# P07_DDR3.net
KiCad netlist of a schematic drawn in Altium Designer
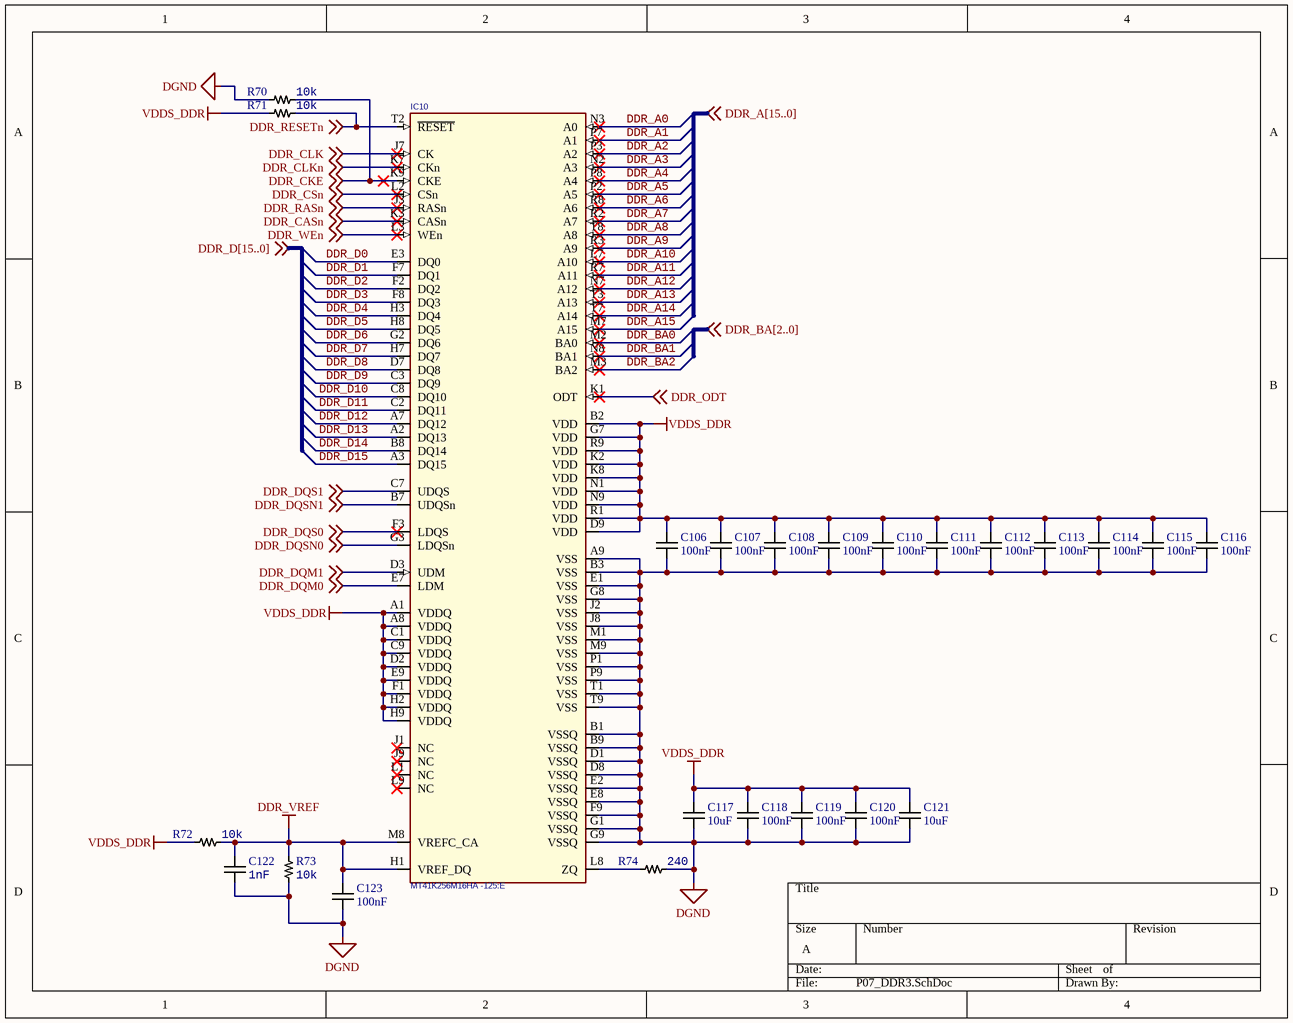
[diagram p0: P07_DDR3.SchDoc]

(export (version "E")
  (design (tool "Eeschema 10.0.6"))
  (components
    (comp (ref "C106")
      (value "C0402C104K4RACTU")
      (footprint "Orient:CAP0402")
      (description "MLCC 100nF 0402 SMD")
      (fields
        (field (name "MANUFACTURER") "KEMET")
        (field (name "CAPACITANCE") "100nF")
        (field (name "TOLERANCE") "10%")
      )
      (libsource (lib "Orient") (part "CAP_100nF"))
    )
    (comp (ref "C107")
      (value "C0402C104K4RACTU")
      (footprint "Orient:CAP0402")
      (description "MLCC 100nF 0402 SMD")
      (fields
        (field (name "MANUFACTURER") "KEMET")
        (field (name "CAPACITANCE") "100nF")
        (field (name "TOLERANCE") "10%")
      )
      (libsource (lib "Orient") (part "CAP_100nF"))
    )
    (comp (ref "C108")
      (value "C0402C104K4RACTU")
      (footprint "Orient:CAP0402")
      (description "MLCC 100nF 0402 SMD")
      (fields
        (field (name "MANUFACTURER") "KEMET")
        (field (name "CAPACITANCE") "100nF")
        (field (name "TOLERANCE") "10%")
      )
      (libsource (lib "Orient") (part "CAP_100nF"))
    )
    (comp (ref "C109")
      (value "C0402C104K4RACTU")
      (footprint "Orient:CAP0402")
      (description "MLCC 100nF 0402 SMD")
      (fields
        (field (name "MANUFACTURER") "KEMET")
        (field (name "CAPACITANCE") "100nF")
        (field (name "TOLERANCE") "10%")
      )
      (libsource (lib "Orient") (part "CAP_100nF"))
    )
    (comp (ref "C110")
      (value "C0402C104K4RACTU")
      (footprint "Orient:CAP0402")
      (description "MLCC 100nF 0402 SMD")
      (fields
        (field (name "MANUFACTURER") "KEMET")
        (field (name "CAPACITANCE") "100nF")
        (field (name "TOLERANCE") "10%")
      )
      (libsource (lib "Orient") (part "CAP_100nF"))
    )
    (comp (ref "C111")
      (value "C0402C104K4RACTU")
      (footprint "Orient:CAP0402")
      (description "MLCC 100nF 0402 SMD")
      (fields
        (field (name "MANUFACTURER") "KEMET")
        (field (name "CAPACITANCE") "100nF")
        (field (name "TOLERANCE") "10%")
      )
      (libsource (lib "Orient") (part "CAP_100nF"))
    )
    (comp (ref "C112")
      (value "C0402C104K4RACTU")
      (footprint "Orient:CAP0402")
      (description "MLCC 100nF 0402 SMD")
      (fields
        (field (name "MANUFACTURER") "KEMET")
        (field (name "CAPACITANCE") "100nF")
        (field (name "TOLERANCE") "10%")
      )
      (libsource (lib "Orient") (part "CAP_100nF"))
    )
    (comp (ref "C113")
      (value "C0402C104K4RACTU")
      (footprint "Orient:CAP0402")
      (description "MLCC 100nF 0402 SMD")
      (fields
        (field (name "MANUFACTURER") "KEMET")
        (field (name "CAPACITANCE") "100nF")
        (field (name "TOLERANCE") "10%")
      )
      (libsource (lib "Orient") (part "CAP_100nF"))
    )
    (comp (ref "C114")
      (value "C0402C104K4RACTU")
      (footprint "Orient:CAP0402")
      (description "MLCC 100nF 0402 SMD")
      (fields
        (field (name "MANUFACTURER") "KEMET")
        (field (name "CAPACITANCE") "100nF")
        (field (name "TOLERANCE") "10%")
      )
      (libsource (lib "Orient") (part "CAP_100nF"))
    )
    (comp (ref "C115")
      (value "C0402C104K4RACTU")
      (footprint "Orient:CAP0402")
      (description "MLCC 100nF 0402 SMD")
      (fields
        (field (name "MANUFACTURER") "KEMET")
        (field (name "CAPACITANCE") "100nF")
        (field (name "TOLERANCE") "10%")
      )
      (libsource (lib "Orient") (part "CAP_100nF"))
    )
    (comp (ref "C116")
      (value "C0402C104K4RACTU")
      (footprint "Orient:CAP0402")
      (description "MLCC 100nF 0402 SMD")
      (fields
        (field (name "MANUFACTURER") "KEMET")
        (field (name "CAPACITANCE") "100nF")
        (field (name "TOLERANCE") "10%")
      )
      (libsource (lib "Orient") (part "CAP_100nF"))
    )
    (comp (ref "C117")
      (value "C2012X6S1A106K085AC")
      (footprint "Orient:CAP0805")
      (description "MLCC 10uF 0805 SMD")
      (fields
        (field (name "MANUFACTURER") "TDK")
        (field (name "CAPACITANCE") "10uF")
        (field (name "TOLERANCE") "10%")
      )
      (libsource (lib "Orient") (part "CAP_10uF"))
    )
    (comp (ref "C118")
      (value "C0402C104K4RACTU")
      (footprint "Orient:CAP0402")
      (description "MLCC 100nF 0402 SMD")
      (fields
        (field (name "MANUFACTURER") "KEMET")
        (field (name "CAPACITANCE") "100nF")
        (field (name "TOLERANCE") "10%")
      )
      (libsource (lib "Orient") (part "CAP_100nF"))
    )
    (comp (ref "C119")
      (value "C0402C104K4RACTU")
      (footprint "Orient:CAP0402")
      (description "MLCC 100nF 0402 SMD")
      (fields
        (field (name "MANUFACTURER") "KEMET")
        (field (name "CAPACITANCE") "100nF")
        (field (name "TOLERANCE") "10%")
      )
      (libsource (lib "Orient") (part "CAP_100nF"))
    )
    (comp (ref "C120")
      (value "C0402C104K4RACTU")
      (footprint "Orient:CAP0402")
      (description "MLCC 100nF 0402 SMD")
      (fields
        (field (name "MANUFACTURER") "KEMET")
        (field (name "CAPACITANCE") "100nF")
        (field (name "TOLERANCE") "10%")
      )
      (libsource (lib "Orient") (part "CAP_100nF"))
    )
    (comp (ref "C121")
      (value "C2012X6S1A106K085AC")
      (footprint "Orient:CAP0805")
      (description "MLCC 10uF 0805 SMD")
      (fields
        (field (name "MANUFACTURER") "TDK")
        (field (name "CAPACITANCE") "10uF")
        (field (name "TOLERANCE") "10%")
      )
      (libsource (lib "Orient") (part "CAP_10uF"))
    )
    (comp (ref "C122")
      (value "CC0402KRX7R9BB102")
      (footprint "Orient:CAP0402")
      (description "MLCC 1nF 0402 SMD")
      (fields
        (field (name "MANUFACTURER") "Yageo")
        (field (name "TOLERANCE") "10%")
        (field (name "CAPACITANCE") "1nF")
      )
      (libsource (lib "Orient") (part "CAP_1nF"))
    )
    (comp (ref "C123")
      (value "C0402C104K4RACTU")
      (footprint "Orient:CAP0402")
      (description "MLCC 100nF 0402 SMD")
      (fields
        (field (name "MANUFACTURER") "KEMET")
        (field (name "CAPACITANCE") "100nF")
        (field (name "TOLERANCE") "10%")
      )
      (libsource (lib "Orient") (part "CAP_100nF"))
    )
    (comp (ref "IC10")
      (value "MT41K256M16HA -125:E")
      (footprint "Orient:BGA96_T9_P8_9X14")
      (description "DDR2 SDRAM 2Gb (256Mx8)")
      (fields
        (field (name "MANUFACTURER") "Micron Technology")
        (field (name "MANUFACTURER PART NUMBER") "MT41K256M16HA-125:E")
      )
      (libsource (lib "Orient") (part "MT41K256M16HA"))
    )
    (comp (ref "R70")
      (value "RC0402FR-0710KL")
      (footprint "Orient:RES0402")
      (description "Resistor 10kOhm 0402 SMD")
      (fields
        (field (name "MANUFACTURER") "Yageo")
        (field (name "TOLERANCE") "1%")
        (field (name "RESISTANCE") "10k")
      )
      (libsource (lib "Orient") (part "RES_10k"))
    )
    (comp (ref "R71")
      (value "RC0402FR-0710KL")
      (footprint "Orient:RES0402")
      (description "Resistor 10kOhm 0402 SMD")
      (fields
        (field (name "MANUFACTURER") "Yageo")
        (field (name "TOLERANCE") "1%")
        (field (name "RESISTANCE") "10k")
      )
      (libsource (lib "Orient") (part "RES_10k"))
    )
    (comp (ref "R72")
      (value "RC0402FR-0710KL")
      (footprint "Orient:RES0402")
      (description "Resistor 10kOhm 0402 SMD")
      (fields
        (field (name "MANUFACTURER") "Yageo")
        (field (name "TOLERANCE") "1%")
        (field (name "RESISTANCE") "10k")
      )
      (libsource (lib "Orient") (part "RES_10k"))
    )
    (comp (ref "R73")
      (value "RC0402FR-0710KL")
      (footprint "Orient:RES0402")
      (description "Resistor 10kOhm 0402 SMD")
      (fields
        (field (name "MANUFACTURER") "Yageo")
        (field (name "TOLERANCE") "1%")
        (field (name "RESISTANCE") "10k")
      )
      (libsource (lib "Orient") (part "RES_10k"))
    )
    (comp (ref "R74")
      (value "RC0402FR-07240RL")
      (footprint "Orient:RES0402")
      (description "Resistor 240Ohm 0402 SMD")
      (fields
        (field (name "MANUFACTURER") "Yageo Phycomp")
        (field (name "TOLERANCE") "1%")
        (field (name "RESISTANCE") "240")
      )
      (libsource (lib "Orient") (part "RES_240"))
    )
  )
  (nets
    (net (code "1") (name "DDR_A0") (class "Default")
      (node (ref "IC10") (pin "N3") (pinfunction "A0_N3") (pintype "input+no_connect"))
    )
    (net (code "2") (name "DDR_A1") (class "Default")
      (node (ref "IC10") (pin "P7") (pinfunction "A1_P7") (pintype "input+no_connect"))
    )
    (net (code "3") (name "DDR_A2") (class "Default")
      (node (ref "IC10") (pin "P3") (pinfunction "A2_P3") (pintype "input+no_connect"))
    )
    (net (code "4") (name "DDR_A3") (class "Default")
      (node (ref "IC10") (pin "N2") (pinfunction "A3_N2") (pintype "input+no_connect"))
    )
    (net (code "5") (name "DDR_A4") (class "Default")
      (node (ref "IC10") (pin "P8") (pinfunction "A4_P8") (pintype "input+no_connect"))
    )
    (net (code "6") (name "DDR_A5") (class "Default")
      (node (ref "IC10") (pin "P2") (pinfunction "A5_P2") (pintype "input+no_connect"))
    )
    (net (code "7") (name "DDR_A6") (class "Default")
      (node (ref "IC10") (pin "R8") (pinfunction "A6_R8") (pintype "input+no_connect"))
    )
    (net (code "8") (name "DDR_A7") (class "Default")
      (node (ref "IC10") (pin "R2") (pinfunction "A7_R2") (pintype "input+no_connect"))
    )
    (net (code "9") (name "DDR_A8") (class "Default")
      (node (ref "IC10") (pin "T8") (pinfunction "A8_T8") (pintype "input+no_connect"))
    )
    (net (code "10") (name "DDR_A9") (class "Default")
      (node (ref "IC10") (pin "R3") (pinfunction "A9_R3") (pintype "input+no_connect"))
    )
    (net (code "11") (name "DDR_A10") (class "Default")
      (node (ref "IC10") (pin "L7") (pinfunction "A10_L7") (pintype "input+no_connect"))
    )
    (net (code "12") (name "DDR_A11") (class "Default")
      (node (ref "IC10") (pin "R7") (pinfunction "A11_R7") (pintype "input+no_connect"))
    )
    (net (code "13") (name "DDR_A12") (class "Default")
      (node (ref "IC10") (pin "N7") (pinfunction "A12_N7") (pintype "input+no_connect"))
    )
    (net (code "14") (name "DDR_A13") (class "Default")
      (node (ref "IC10") (pin "T3") (pinfunction "A13_T3") (pintype "input+no_connect"))
    )
    (net (code "15") (name "DDR_A14") (class "Default")
      (node (ref "IC10") (pin "T7") (pinfunction "A14_T7") (pintype "input+no_connect"))
    )
    (net (code "16") (name "DDR_A15") (class "Default")
      (node (ref "IC10") (pin "M7") (pinfunction "A15_M7") (pintype "input+no_connect"))
    )
    (net (code "18") (name "DDR_BA0") (class "Default")
      (node (ref "IC10") (pin "M2") (pinfunction "BA0_M2") (pintype "input+no_connect"))
    )
    (net (code "19") (name "DDR_BA1") (class "Default")
      (node (ref "IC10") (pin "N8") (pinfunction "BA1_N8") (pintype "input+no_connect"))
    )
    (net (code "20") (name "DDR_BA2") (class "Default")
      (node (ref "IC10") (pin "M3") (pinfunction "BA2_M3") (pintype "input+no_connect"))
    )
    (net (code "22") (name "DDR_CASn") (class "Default")
      (node (ref "IC10") (pin "K3") (pinfunction "CASn_K3") (pintype "input"))
    )
    (net (code "23") (name "DDR_CKE") (class "Default")
      (node (ref "IC10") (pin "K9") (pinfunction "CKE_K9") (pintype "input"))
      (node (ref "R70") (pin "1") (pintype "passive"))
    )
    (net (code "24") (name "DDR_CLK") (class "Default")
      (node (ref "IC10") (pin "J7") (pinfunction "CK_J7") (pintype "input"))
    )
    (net (code "25") (name "DDR_CLKn") (class "Default")
      (node (ref "IC10") (pin "K7") (pinfunction "CKn_K7") (pintype "input"))
    )
    (net (code "26") (name "DDR_CSn") (class "Default")
      (node (ref "IC10") (pin "L2") (pinfunction "CSn_L2") (pintype "input"))
    )
    (net (code "27") (name "DDR_D0") (class "Default")
      (node (ref "IC10") (pin "E3") (pinfunction "DQ0_E3") (pintype "bidirectional"))
    )
    (net (code "28") (name "DDR_D1") (class "Default")
      (node (ref "IC10") (pin "F7") (pinfunction "DQ1_F7") (pintype "bidirectional"))
    )
    (net (code "29") (name "DDR_D2") (class "Default")
      (node (ref "IC10") (pin "F2") (pinfunction "DQ2_F2") (pintype "bidirectional"))
    )
    (net (code "30") (name "DDR_D3") (class "Default")
      (node (ref "IC10") (pin "F8") (pinfunction "DQ3_F8") (pintype "bidirectional"))
    )
    (net (code "31") (name "DDR_D4") (class "Default")
      (node (ref "IC10") (pin "H3") (pinfunction "DQ4_H3") (pintype "bidirectional"))
    )
    (net (code "32") (name "DDR_D5") (class "Default")
      (node (ref "IC10") (pin "H8") (pinfunction "DQ5_H8") (pintype "bidirectional"))
    )
    (net (code "33") (name "DDR_D6") (class "Default")
      (node (ref "IC10") (pin "G2") (pinfunction "DQ6_G2") (pintype "bidirectional"))
    )
    (net (code "34") (name "DDR_D7") (class "Default")
      (node (ref "IC10") (pin "H7") (pinfunction "DQ7_H7") (pintype "bidirectional"))
    )
    (net (code "35") (name "DDR_D8") (class "Default")
      (node (ref "IC10") (pin "D7") (pinfunction "DQ8_D7") (pintype "bidirectional"))
    )
    (net (code "36") (name "DDR_D9") (class "Default")
      (node (ref "IC10") (pin "C3") (pinfunction "DQ9_C3") (pintype "bidirectional"))
    )
    (net (code "37") (name "DDR_D10") (class "Default")
      (node (ref "IC10") (pin "C8") (pinfunction "DQ10_C8") (pintype "bidirectional"))
    )
    (net (code "38") (name "DDR_D11") (class "Default")
      (node (ref "IC10") (pin "C2") (pinfunction "DQ11_C2") (pintype "bidirectional"))
    )
    (net (code "39") (name "DDR_D12") (class "Default")
      (node (ref "IC10") (pin "A7") (pinfunction "DQ12_A7") (pintype "bidirectional"))
    )
    (net (code "40") (name "DDR_D13") (class "Default")
      (node (ref "IC10") (pin "A2") (pinfunction "DQ13_A2") (pintype "bidirectional"))
    )
    (net (code "41") (name "DDR_D14") (class "Default")
      (node (ref "IC10") (pin "B8") (pinfunction "DQ14_B8") (pintype "bidirectional"))
    )
    (net (code "42") (name "DDR_D15") (class "Default")
      (node (ref "IC10") (pin "A3") (pinfunction "DQ15_A3") (pintype "bidirectional"))
    )
    (net (code "43") (name "DDR_DQM0") (class "Default")
      (node (ref "IC10") (pin "E7") (pinfunction "LDM_E7") (pintype "bidirectional"))
    )
    (net (code "44") (name "DDR_DQM1") (class "Default")
      (node (ref "IC10") (pin "D3") (pinfunction "UDM_D3") (pintype "input"))
    )
    (net (code "45") (name "DDR_DQS0") (class "Default")
      (node (ref "IC10") (pin "F3") (pinfunction "LDQS_F3") (pintype "bidirectional"))
    )
    (net (code "46") (name "DDR_DQS1") (class "Default")
      (node (ref "IC10") (pin "C7") (pinfunction "UDQS_C7") (pintype "bidirectional"))
    )
    (net (code "47") (name "DDR_DQSN0") (class "Default")
      (node (ref "IC10") (pin "G3") (pinfunction "LDQSn_G3") (pintype "bidirectional"))
    )
    (net (code "48") (name "DDR_DQSN1") (class "Default")
      (node (ref "IC10") (pin "B7") (pinfunction "UDQSn_B7") (pintype "bidirectional"))
    )
    (net (code "50") (name "DDR_ODT") (class "Default")
      (node (ref "IC10") (pin "K1") (pinfunction "ODT_K1") (pintype "input"))
    )
    (net (code "51") (name "DDR_RASn") (class "Default")
      (node (ref "IC10") (pin "J3") (pinfunction "RASn_J3") (pintype "input"))
    )
    (net (code "52") (name "DDR_RESETn") (class "Default")
      (node (ref "IC10") (pin "T2") (pinfunction "~{RESET}_T2") (pintype "input"))
      (node (ref "R71") (pin "1") (pintype "passive"))
    )
    (net (code "53") (name "DDR_VREF") (class "Default")
      (node (ref "C122") (pin "1") (pintype "passive"))
      (node (ref "C123") (pin "1") (pintype "passive"))
      (node (ref "IC10") (pin "H1") (pinfunction "VREF_DQ_H1") (pintype "passive"))
      (node (ref "IC10") (pin "M8") (pinfunction "VREFC_CA_M8") (pintype "power_in"))
      (node (ref "R72") (pin "1") (pintype "passive"))
      (node (ref "R73") (pin "2") (pintype "passive"))
    )
    (net (code "54") (name "DDR_WEn") (class "Default")
      (node (ref "IC10") (pin "L3") (pinfunction "WEn_L3") (pintype "input"))
    )
    (net (code "55") (name "DGND") (class "Default")
      (node (ref "C106") (pin "2") (pintype "passive"))
      (node (ref "C107") (pin "2") (pintype "passive"))
      (node (ref "C108") (pin "2") (pintype "passive"))
      (node (ref "C109") (pin "2") (pintype "passive"))
      (node (ref "C110") (pin "2") (pintype "passive"))
      (node (ref "C111") (pin "2") (pintype "passive"))
      (node (ref "C112") (pin "2") (pintype "passive"))
      (node (ref "C113") (pin "2") (pintype "passive"))
      (node (ref "C114") (pin "2") (pintype "passive"))
      (node (ref "C115") (pin "2") (pintype "passive"))
      (node (ref "C116") (pin "2") (pintype "passive"))
      (node (ref "C117") (pin "1") (pintype "passive"))
      (node (ref "C118") (pin "2") (pintype "passive"))
      (node (ref "C119") (pin "2") (pintype "passive"))
      (node (ref "C120") (pin "2") (pintype "passive"))
      (node (ref "C121") (pin "1") (pintype "passive"))
      (node (ref "C122") (pin "2") (pintype "passive"))
      (node (ref "C123") (pin "2") (pintype "passive"))
      (node (ref "IC10") (pin "A9") (pinfunction "VSS_A9") (pintype "power_in"))
      (node (ref "IC10") (pin "B1") (pinfunction "VSSQ_B1") (pintype "power_in"))
      (node (ref "IC10") (pin "B3") (pinfunction "VSS_B3") (pintype "power_in"))
      (node (ref "IC10") (pin "B9") (pinfunction "VSSQ_B9") (pintype "power_in"))
      (node (ref "IC10") (pin "D1") (pinfunction "VSSQ_D1") (pintype "power_in"))
      (node (ref "IC10") (pin "D8") (pinfunction "VSSQ_D8") (pintype "power_in"))
      (node (ref "IC10") (pin "E1") (pinfunction "VSS_E1") (pintype "power_in"))
      (node (ref "IC10") (pin "E2") (pinfunction "VSSQ_E2") (pintype "power_in"))
      (node (ref "IC10") (pin "E8") (pinfunction "VSSQ_E8") (pintype "power_in"))
      (node (ref "IC10") (pin "F9") (pinfunction "VSSQ_F9") (pintype "power_in"))
      (node (ref "IC10") (pin "G1") (pinfunction "VSSQ_G1") (pintype "power_in"))
      (node (ref "IC10") (pin "G8") (pinfunction "VSS_G8") (pintype "power_in"))
      (node (ref "IC10") (pin "G9") (pinfunction "VSSQ_G9") (pintype "power_in"))
      (node (ref "IC10") (pin "J2") (pinfunction "VSS_J2") (pintype "power_in"))
      (node (ref "IC10") (pin "J8") (pinfunction "VSS_J8") (pintype "power_in"))
      (node (ref "IC10") (pin "M1") (pinfunction "VSS_M1") (pintype "power_in"))
      (node (ref "IC10") (pin "M9") (pinfunction "VSS_M9") (pintype "power_in"))
      (node (ref "IC10") (pin "P1") (pinfunction "VSS_P1") (pintype "power_in"))
      (node (ref "IC10") (pin "P9") (pinfunction "VSS_P9") (pintype "power_in"))
      (node (ref "IC10") (pin "T1") (pinfunction "VSS_T1") (pintype "power_in"))
      (node (ref "IC10") (pin "T9") (pinfunction "VSS_T9") (pintype "power_in"))
      (node (ref "R70") (pin "2") (pintype "passive"))
      (node (ref "R73") (pin "1") (pintype "passive"))
      (node (ref "R74") (pin "2") (pintype "passive"))
    )
    (net (code "56") (name "Net-(IC10-ZQ)") (class "Default")
      (node (ref "IC10") (pin "L8") (pinfunction "ZQ_L8") (pintype "passive"))
      (node (ref "R74") (pin "1") (pintype "passive"))
    )
    (net (code "57") (name "VDDS_DDR") (class "Default")
      (node (ref "C106") (pin "1") (pintype "passive"))
      (node (ref "C107") (pin "1") (pintype "passive"))
      (node (ref "C108") (pin "1") (pintype "passive"))
      (node (ref "C109") (pin "1") (pintype "passive"))
      (node (ref "C110") (pin "1") (pintype "passive"))
      (node (ref "C111") (pin "1") (pintype "passive"))
      (node (ref "C112") (pin "1") (pintype "passive"))
      (node (ref "C113") (pin "1") (pintype "passive"))
      (node (ref "C114") (pin "1") (pintype "passive"))
      (node (ref "C115") (pin "1") (pintype "passive"))
      (node (ref "C116") (pin "1") (pintype "passive"))
      (node (ref "C117") (pin "2") (pintype "passive"))
      (node (ref "C118") (pin "1") (pintype "passive"))
      (node (ref "C119") (pin "1") (pintype "passive"))
      (node (ref "C120") (pin "1") (pintype "passive"))
      (node (ref "C121") (pin "2") (pintype "passive"))
      (node (ref "IC10") (pin "A1") (pinfunction "VDDQ_A1") (pintype "power_in"))
      (node (ref "IC10") (pin "A8") (pinfunction "VDDQ_A8") (pintype "power_in"))
      (node (ref "IC10") (pin "B2") (pinfunction "VDD_B2") (pintype "power_in"))
      (node (ref "IC10") (pin "C1") (pinfunction "VDDQ_C1") (pintype "power_in"))
      (node (ref "IC10") (pin "C9") (pinfunction "VDDQ_C9") (pintype "power_in"))
      (node (ref "IC10") (pin "D2") (pinfunction "VDDQ_D2") (pintype "power_in"))
      (node (ref "IC10") (pin "D9") (pinfunction "VDD_D9") (pintype "power_in"))
      (node (ref "IC10") (pin "E9") (pinfunction "VDDQ_E9") (pintype "power_in"))
      (node (ref "IC10") (pin "F1") (pinfunction "VDDQ_F1") (pintype "power_in"))
      (node (ref "IC10") (pin "G7") (pinfunction "VDD_G7") (pintype "power_in"))
      (node (ref "IC10") (pin "H2") (pinfunction "VDDQ_H2") (pintype "power_in"))
      (node (ref "IC10") (pin "H9") (pinfunction "VDDQ_H9") (pintype "power_in"))
      (node (ref "IC10") (pin "K2") (pinfunction "VDD_K2") (pintype "power_in"))
      (node (ref "IC10") (pin "K8") (pinfunction "VDD_K8") (pintype "power_in"))
      (node (ref "IC10") (pin "N1") (pinfunction "VDD_N1") (pintype "power_in"))
      (node (ref "IC10") (pin "N9") (pinfunction "VDD_N9") (pintype "power_in"))
      (node (ref "IC10") (pin "R1") (pinfunction "VDD_R1") (pintype "power_in"))
      (node (ref "IC10") (pin "R9") (pinfunction "VDD_R9") (pintype "power_in"))
      (node (ref "R71") (pin "2") (pintype "passive"))
      (node (ref "R72") (pin "2") (pintype "passive"))
    )
    (net (code "58") (name "unconnected-(IC10-NC-PadJ1)") (class "Default")
      (node (ref "IC10") (pin "J1") (pinfunction "NC_J1") (pintype "passive+no_connect"))
    )
    (net (code "59") (name "unconnected-(IC10-NC-PadJ9)") (class "Default")
      (node (ref "IC10") (pin "J9") (pinfunction "NC_J9") (pintype "passive+no_connect"))
    )
    (net (code "60") (name "unconnected-(IC10-NC-PadL1)") (class "Default")
      (node (ref "IC10") (pin "L1") (pinfunction "NC_L1") (pintype "power_in+no_connect"))
    )
    (net (code "61") (name "unconnected-(IC10-NC-PadL9)") (class "Default")
      (node (ref "IC10") (pin "L9") (pinfunction "NC_L9") (pintype "power_in+no_connect"))
    )
  )
)
